# CLK_SW.net
KiCad netlist of a schematic drawn in Altium Designer
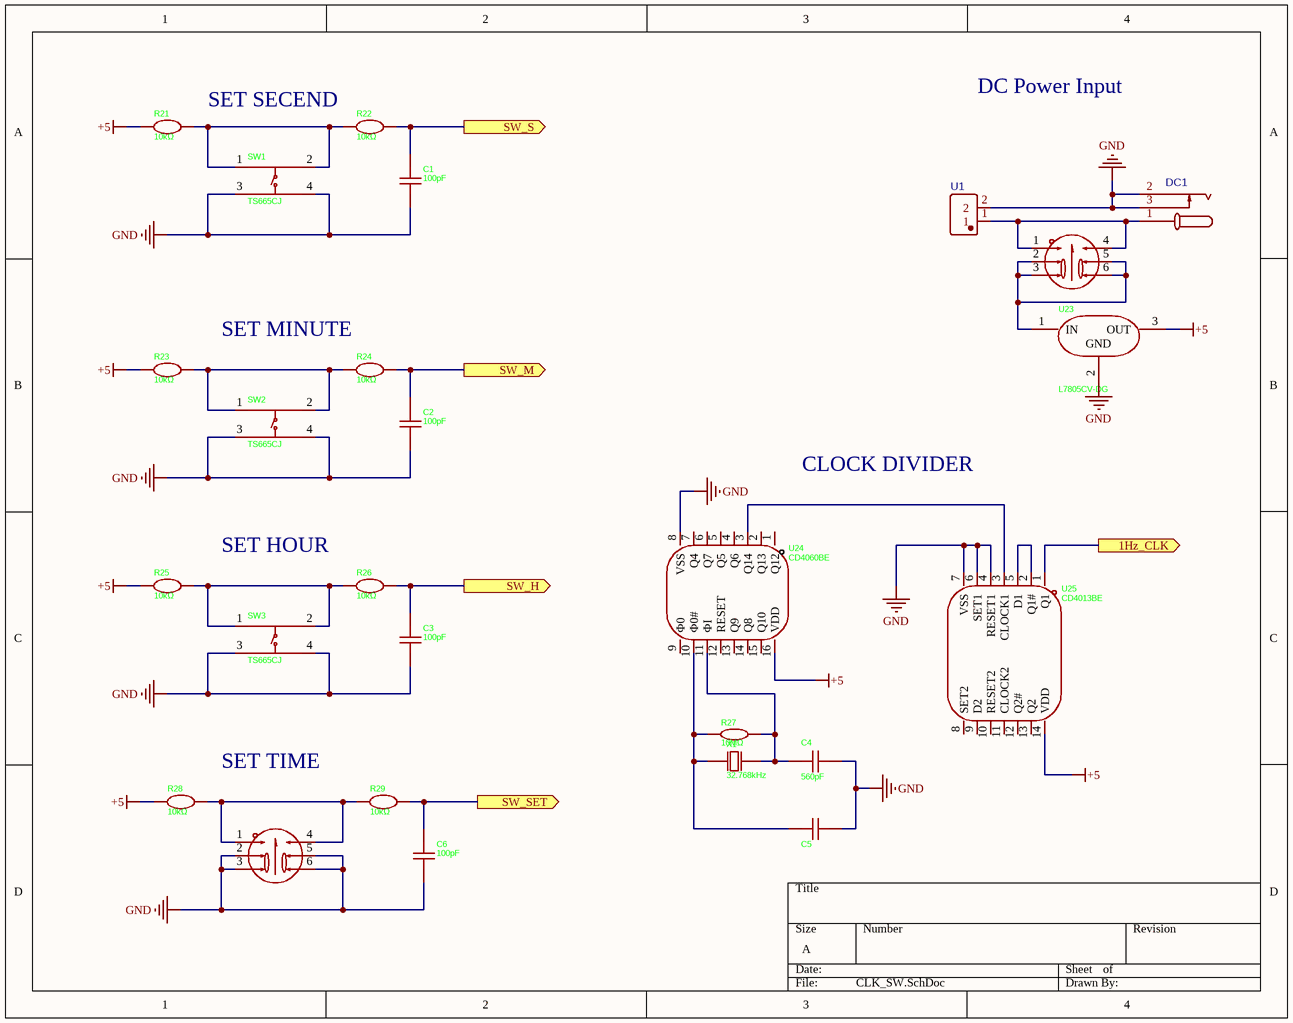
[diagram p0: CLK_SW.SchDoc]

(export (version "E")
  (design (tool "Eeschema 10.0.6"))
  (components
    (comp (ref "C1")
      (value "100pF")
      (footprint "CAP-TH_L5.0-W3.0-P5.00-D0.6-S2.45")
      (fields
        (field (name "MANUFACTURER") "SHM(南方宏明)")
        (field (name "MANUFACTURER PART") "DCT101K20Y5PF6FJ5A0")
        (field (name "TOLERANCE") "±10%")
      )
      (libsource (lib "BCD_Clock_SCH_lib") (part "Cap_100pF_50V_ceramic"))
    )
    (comp (ref "C2")
      (value "100pF")
      (footprint "CAP-TH_L5.0-W3.0-P5.00-D0.6-S2.45")
      (fields
        (field (name "MANUFACTURER") "SHM(南方宏明)")
        (field (name "MANUFACTURER PART") "DCT101K20Y5PF6FJ5A0")
        (field (name "TOLERANCE") "±10%")
      )
      (libsource (lib "BCD_Clock_SCH_lib") (part "Cap_100pF_50V_ceramic"))
    )
    (comp (ref "C3")
      (value "100pF")
      (footprint "CAP-TH_L5.0-W3.0-P5.00-D0.6-S2.45")
      (fields
        (field (name "MANUFACTURER") "SHM(南方宏明)")
        (field (name "MANUFACTURER PART") "DCT101K20Y5PF6FJ5A0")
        (field (name "TOLERANCE") "±10%")
      )
      (libsource (lib "BCD_Clock_SCH_lib") (part "Cap_100pF_50V_ceramic"))
    )
    (comp (ref "C4")
      (value "560pF")
      (footprint "CAP-TH_L8.5-W3.0-P5.00-D0.6-S2.5")
      (fields
        (field (name "MANUFACTURER") "SHM(南方宏明)")
        (field (name "MANUFACTURER PART") "DCC561J34SL F6FJ5A0")
        (field (name "TOLERANCE") "±5%")
      )
      (libsource (lib "BCD_Clock_SCH_lib") (part "Cap_560pF_50V_ceraic"))
    )
    (comp (ref "C5")
      (value "22pF")
      (footprint "CAP-TH_L7.4-W4.0-P6.40-D0.5-S1.00")
      (fields
        (field (name "MANUFACTURER") "Dersonic(德尔创)")
        (field (name "MANUFACTURER PART") "CC1H220KA1EDCH4B1100")
        (field (name "TOLERANCE") "±10%")
      )
      (libsource (lib "BCD_Clock_SCH_lib") (part "Cap_22pF_50V_ceramic"))
    )
    (comp (ref "C6")
      (value "100pF")
      (footprint "CAP-TH_L5.0-W3.0-P5.00-D0.6-S2.45")
      (fields
        (field (name "MANUFACTURER") "SHM(南方宏明)")
        (field (name "MANUFACTURER PART") "DCT101K20Y5PF6FJ5A0")
        (field (name "TOLERANCE") "±10%")
      )
      (libsource (lib "BCD_Clock_SCH_lib") (part "Cap_100pF_50V_ceramic"))
    )
    (comp (ref "DC1")
      (value "DC-005-2.5A-2.0")
      (footprint "CONN-TH_DC-005-2.5A-2.0")
      (fields (field (name "MANUFACTURER") "XKB Connection(中国星坤)") (field (name "CONTRIBUTOR") "LCSC"))
      (libsource (lib "BCD_Clock_SCH_lib") (part "DC-005-2.5A-2.0"))
    )
    (comp (ref "R21")
      (value "10kΩ")
      (footprint "RES-TH_BD2.4-L6.3-P10.30-D0.6")
      (fields
        (field (name "MANUFACTURER") "Tyohm(幸亚电阻)")
        (field (name "MANUFACTURER PART") "RN1/4W10KFT/BA1")
        (field (name "TOLERANCE") "±1%")
      )
      (libsource (lib "BCD_Clock_SCH_lib") (part "Reg_10k_0.25W"))
    )
    (comp (ref "R22")
      (value "10kΩ")
      (footprint "RES-TH_BD2.4-L6.3-P10.30-D0.6")
      (fields
        (field (name "MANUFACTURER") "Tyohm(幸亚电阻)")
        (field (name "MANUFACTURER PART") "RN1/4W10KFT/BA1")
        (field (name "TOLERANCE") "±1%")
      )
      (libsource (lib "BCD_Clock_SCH_lib") (part "Reg_10k_0.25W"))
    )
    (comp (ref "R23")
      (value "10kΩ")
      (footprint "RES-TH_BD2.4-L6.3-P10.30-D0.6")
      (fields
        (field (name "MANUFACTURER") "Tyohm(幸亚电阻)")
        (field (name "MANUFACTURER PART") "RN1/4W10KFT/BA1")
        (field (name "TOLERANCE") "±1%")
      )
      (libsource (lib "BCD_Clock_SCH_lib") (part "Reg_10k_0.25W"))
    )
    (comp (ref "R24")
      (value "10kΩ")
      (footprint "RES-TH_BD2.4-L6.3-P10.30-D0.6")
      (fields
        (field (name "MANUFACTURER") "Tyohm(幸亚电阻)")
        (field (name "MANUFACTURER PART") "RN1/4W10KFT/BA1")
        (field (name "TOLERANCE") "±1%")
      )
      (libsource (lib "BCD_Clock_SCH_lib") (part "Reg_10k_0.25W"))
    )
    (comp (ref "R25")
      (value "10kΩ")
      (footprint "RES-TH_BD2.4-L6.3-P10.30-D0.6")
      (fields
        (field (name "MANUFACTURER") "Tyohm(幸亚电阻)")
        (field (name "MANUFACTURER PART") "RN1/4W10KFT/BA1")
        (field (name "TOLERANCE") "±1%")
      )
      (libsource (lib "BCD_Clock_SCH_lib") (part "Reg_10k_0.25W"))
    )
    (comp (ref "R26")
      (value "10kΩ")
      (footprint "RES-TH_BD2.4-L6.3-P10.30-D0.6")
      (fields
        (field (name "MANUFACTURER") "Tyohm(幸亚电阻)")
        (field (name "MANUFACTURER PART") "RN1/4W10KFT/BA1")
        (field (name "TOLERANCE") "±1%")
      )
      (libsource (lib "BCD_Clock_SCH_lib") (part "Reg_10k_0.25W"))
    )
    (comp (ref "R27")
      (value "10MΩ")
      (footprint "RES-TH_BD2.2-L6.5-P10.50-D0.6")
      (fields
        (field (name "MANUFACTURER") "CCO(千志电子)")
        (field (name "MANUFACTURER PART") "CF1/4W-10MΩ±5% T")
        (field (name "TOLERANCE") "±5%")
      )
      (libsource (lib "BCD_Clock_SCH_lib") (part "Reg_10M_0.25W"))
    )
    (comp (ref "R28")
      (value "10kΩ")
      (footprint "RES-TH_BD2.4-L6.3-P10.30-D0.6")
      (fields
        (field (name "MANUFACTURER") "Tyohm(幸亚电阻)")
        (field (name "MANUFACTURER PART") "RN1/4W10KFT/BA1")
        (field (name "TOLERANCE") "±1%")
      )
      (libsource (lib "BCD_Clock_SCH_lib") (part "Reg_10k_0.25W"))
    )
    (comp (ref "R29")
      (value "10kΩ")
      (footprint "RES-TH_BD2.4-L6.3-P10.30-D0.6")
      (fields
        (field (name "MANUFACTURER") "Tyohm(幸亚电阻)")
        (field (name "MANUFACTURER PART") "RN1/4W10KFT/BA1")
        (field (name "TOLERANCE") "±1%")
      )
      (libsource (lib "BCD_Clock_SCH_lib") (part "Reg_10k_0.25W"))
    )
    (comp (ref "SW1")
      (value "TS665CJ")
      (footprint "SW-TH_4P-L6.0-W6.0-P4.50-LS6.5")
      (fields (field (name "MANUFACTURER") "SHOU HAN(首韩)"))
      (libsource (lib "BCD_Clock_SCH_lib") (part "TS665CJ"))
    )
    (comp (ref "SW2")
      (value "TS665CJ")
      (footprint "SW-TH_4P-L6.0-W6.0-P4.50-LS6.5")
      (fields (field (name "MANUFACTURER") "SHOU HAN(首韩)"))
      (libsource (lib "BCD_Clock_SCH_lib") (part "TS665CJ"))
    )
    (comp (ref "SW3")
      (value "TS665CJ")
      (footprint "SW-TH_4P-L6.0-W6.0-P4.50-LS6.5")
      (fields (field (name "MANUFACTURER") "SHOU HAN(首韩)"))
      (libsource (lib "BCD_Clock_SCH_lib") (part "TS665CJ"))
    )
    (comp (ref "U1")
      (value "DBT50G-7.62-2P")
      (footprint "CONN-TH_2P-P7.62_L15.2-W16.7-EX4.2")
      (fields
        (field (name "MANUFACTURER") "DORABO(地博电气)")
        (field (name "MANUFACTURER PART") "DBT50G-7.62-2P-BK-P")
        (field (name "CONTRIBUTOR") "LCSC")
      )
      (libsource (lib "BCD_Clock_SCH_lib") (part "DBT50G-7.62-2P"))
    )
    (comp (ref "U22")
      (value "PS-7054DVB-6PL")
      (footprint "SW-TH_6P-L7.0-W7.0-P2.00")
      (fields (field (name "MANUFACTURER") "G-Switch(品赞)"))
      (libsource (lib "BCD_Clock_SCH_lib") (part "PS-7054DVB-6PL"))
    )
    (comp (ref "U23")
      (value "L7805CV-DG")
      (footprint "TO-220-3_L10.0-W4.5-P2.54-L")
      (fields (field (name "MANUFACTURER") "ST(意法半导体)"))
      (libsource (lib "BCD_Clock_SCH_lib") (part "L7805CV-DG"))
    )
    (comp (ref "U24")
      (value "CD4060BE")
      (footprint "DIP-16_L19.8-W6.5-P2.54-LS7.6-BL")
      (fields (field (name "MANUFACTURER") "HGSEMI(华冠)"))
      (libsource (lib "BCD_Clock_SCH_lib") (part "CD4060BE"))
    )
    (comp (ref "U25")
      (value "CD4013BE")
      (footprint "DIP-14_L19.2-W6.6-P2.54-LS10.9-BL")
      (fields (field (name "MANUFACTURER") "TI(德州仪器)"))
      (libsource (lib "BCD_Clock_SCH_lib") (part "CD4013BE"))
    )
    (comp (ref "U26")
      (value "PS-7054DVB-6PL")
      (footprint "SW-TH_6P-L7.0-W7.0-P2.00")
      (fields (field (name "MANUFACTURER") "G-Switch(品赞)"))
      (libsource (lib "BCD_Clock_SCH_lib") (part "PS-7054DVB-6PL"))
    )
    (comp (ref "X1")
      (value "32.768kHz")
      (footprint "OSC-TH_BD3.1-P0.8-D0.3")
      (fields (field (name "MANUFACTURER") "ABRACON") (field (name "MANUFACTURER PART") "AB38T-32.768KHZ"))
      (libsource (lib "BCD_Clock_SCH_lib") (part "AB38T-32.768KHZ"))
    )
  )
  (nets
    (net (code "1") (name "+5") (class "Default")
      (node (ref "R21") (pin "2") (pinfunction "2_2") (pintype "passive"))
      (node (ref "R23") (pin "2") (pinfunction "2_2") (pintype "passive"))
      (node (ref "R25") (pin "2") (pinfunction "2_2") (pintype "passive"))
      (node (ref "R28") (pin "2") (pinfunction "2_2") (pintype "passive"))
      (node (ref "U23") (pin "3") (pinfunction "OUT_3") (pintype "passive"))
      (node (ref "U24") (pin "16") (pinfunction "VDD_16") (pintype "passive"))
      (node (ref "U25") (pin "14") (pinfunction "VDD_14") (pintype "passive"))
    )
    (net (code "2") (name "/1Hz_CLK") (class "Default")
      (node (ref "U25") (pin "1") (pinfunction "Q1_1") (pintype "passive"))
    )
    (net (code "3") (name "/SW_H") (class "Default")
      (node (ref "C3") (pin "2") (pinfunction "2_2") (pintype "passive"))
      (node (ref "R26") (pin "1") (pinfunction "1_1") (pintype "passive"))
    )
    (net (code "4") (name "/SW_M") (class "Default")
      (node (ref "C2") (pin "2") (pinfunction "2_2") (pintype "passive"))
      (node (ref "R24") (pin "1") (pinfunction "1_1") (pintype "passive"))
    )
    (net (code "5") (name "/SW_S") (class "Default")
      (node (ref "C1") (pin "2") (pinfunction "2_2") (pintype "passive"))
      (node (ref "R22") (pin "1") (pinfunction "1_1") (pintype "passive"))
    )
    (net (code "6") (name "/SW_SET") (class "Default")
      (node (ref "C6") (pin "2") (pinfunction "2_2") (pintype "passive"))
      (node (ref "R29") (pin "1") (pinfunction "1_1") (pintype "passive"))
    )
    (net (code "7") (name "GND") (class "Default")
      (node (ref "C1") (pin "1") (pinfunction "1_1") (pintype "passive"))
      (node (ref "C2") (pin "1") (pinfunction "1_1") (pintype "passive"))
      (node (ref "C3") (pin "1") (pinfunction "1_1") (pintype "passive"))
      (node (ref "C4") (pin "1") (pinfunction "1_1") (pintype "passive"))
      (node (ref "C5") (pin "1") (pinfunction "1_1") (pintype "passive"))
      (node (ref "C6") (pin "1") (pinfunction "1_1") (pintype "passive"))
      (node (ref "DC1") (pin "2") (pinfunction "2_2") (pintype "passive"))
      (node (ref "DC1") (pin "3") (pinfunction "3_3") (pintype "passive"))
      (node (ref "SW1") (pin "3") (pinfunction "C_3") (pintype "passive"))
      (node (ref "SW1") (pin "4") (pinfunction "D_4") (pintype "passive"))
      (node (ref "SW2") (pin "3") (pinfunction "C_3") (pintype "passive"))
      (node (ref "SW2") (pin "4") (pinfunction "D_4") (pintype "passive"))
      (node (ref "SW3") (pin "3") (pinfunction "C_3") (pintype "passive"))
      (node (ref "SW3") (pin "4") (pinfunction "D_4") (pintype "passive"))
      (node (ref "U1") (pin "2") (pinfunction "2_2") (pintype "passive"))
      (node (ref "U23") (pin "2") (pinfunction "GND_2") (pintype "passive"))
      (node (ref "U24") (pin "8") (pinfunction "VSS_8") (pintype "passive"))
      (node (ref "U25") (pin "4") (pinfunction "RESET1_4") (pintype "passive"))
      (node (ref "U25") (pin "6") (pinfunction "SET1_6") (pintype "passive"))
      (node (ref "U25") (pin "7") (pinfunction "VSS_7") (pintype "passive"))
      (node (ref "U26") (pin "2") (pinfunction "2_2") (pintype "passive"))
      (node (ref "U26") (pin "3") (pinfunction "3_3") (pintype "passive"))
      (node (ref "U26") (pin "5") (pinfunction "5_5") (pintype "passive"))
      (node (ref "U26") (pin "6") (pinfunction "6_6") (pintype "passive"))
    )
    (net (code "8") (name "Net-(DC1-Pad1)") (class "Default")
      (node (ref "DC1") (pin "1") (pinfunction "1_1") (pintype "passive"))
      (node (ref "U1") (pin "1") (pinfunction "1_1") (pintype "passive"))
      (node (ref "U22") (pin "1") (pinfunction "1_1") (pintype "passive"))
      (node (ref "U22") (pin "4") (pinfunction "4_4") (pintype "passive"))
    )
    (net (code "9") (name "Net-(R28-Pad1)") (class "Default")
      (node (ref "R28") (pin "1") (pinfunction "1_1") (pintype "passive"))
      (node (ref "R29") (pin "2") (pinfunction "2_2") (pintype "passive"))
      (node (ref "U26") (pin "1") (pinfunction "1_1") (pintype "passive"))
      (node (ref "U26") (pin "4") (pinfunction "4_4") (pintype "passive"))
    )
    (net (code "10") (name "Net-(SW1-A)") (class "Default")
      (node (ref "R21") (pin "1") (pinfunction "1_1") (pintype "passive"))
      (node (ref "R22") (pin "2") (pinfunction "2_2") (pintype "passive"))
      (node (ref "SW1") (pin "1") (pinfunction "A_1") (pintype "passive"))
      (node (ref "SW1") (pin "2") (pinfunction "B_2") (pintype "passive"))
    )
    (net (code "11") (name "Net-(SW2-A)") (class "Default")
      (node (ref "R23") (pin "1") (pinfunction "1_1") (pintype "passive"))
      (node (ref "R24") (pin "2") (pinfunction "2_2") (pintype "passive"))
      (node (ref "SW2") (pin "1") (pinfunction "A_1") (pintype "passive"))
      (node (ref "SW2") (pin "2") (pinfunction "B_2") (pintype "passive"))
    )
    (net (code "12") (name "Net-(SW3-A)") (class "Default")
      (node (ref "R25") (pin "1") (pinfunction "1_1") (pintype "passive"))
      (node (ref "R26") (pin "2") (pinfunction "2_2") (pintype "passive"))
      (node (ref "SW3") (pin "1") (pinfunction "A_1") (pintype "passive"))
      (node (ref "SW3") (pin "2") (pinfunction "B_2") (pintype "passive"))
    )
    (net (code "13") (name "Net-(U23-IN)") (class "Default")
      (node (ref "U22") (pin "2") (pinfunction "2_2") (pintype "passive"))
      (node (ref "U22") (pin "3") (pinfunction "3_3") (pintype "passive"))
      (node (ref "U22") (pin "5") (pinfunction "5_5") (pintype "passive"))
      (node (ref "U22") (pin "6") (pinfunction "6_6") (pintype "passive"))
      (node (ref "U23") (pin "1") (pinfunction "IN_1") (pintype "passive"))
    )
    (net (code "14") (name "Net-(U24-Q14)") (class "Default")
      (node (ref "U24") (pin "3") (pinfunction "Q14_3") (pintype "passive"))
      (node (ref "U25") (pin "3") (pinfunction "CLOCK1_3") (pintype "passive"))
    )
    (net (code "15") (name "Net-(U24-Φ0#)") (class "Default")
      (node (ref "C5") (pin "2") (pinfunction "2_2") (pintype "passive"))
      (node (ref "R27") (pin "2") (pinfunction "2_2") (pintype "passive"))
      (node (ref "U24") (pin "10") (pinfunction "Φ0#_10") (pintype "passive"))
      (node (ref "X1") (pin "1") (pinfunction "OSC1_1") (pintype "passive"))
    )
    (net (code "16") (name "Net-(U24-ΦI)") (class "Default")
      (node (ref "C4") (pin "2") (pinfunction "2_2") (pintype "passive"))
      (node (ref "R27") (pin "1") (pinfunction "1_1") (pintype "passive"))
      (node (ref "U24") (pin "11") (pinfunction "ΦI_11") (pintype "passive"))
      (node (ref "X1") (pin "2") (pinfunction "OSC2_2") (pintype "passive"))
    )
    (net (code "17") (name "Net-(U25-D1)") (class "Default")
      (node (ref "U25") (pin "2") (pinfunction "Q1#_2") (pintype "passive"))
      (node (ref "U25") (pin "5") (pinfunction "D1_5") (pintype "passive"))
    )
    (net (code "18") (name "unconnected-(U24-Q4-Pad7)") (class "Default")
      (node (ref "U24") (pin "7") (pinfunction "Q4_7") (pintype "passive"))
    )
    (net (code "19") (name "unconnected-(U24-Q5-Pad5)") (class "Default")
      (node (ref "U24") (pin "5") (pinfunction "Q5_5") (pintype "passive"))
    )
    (net (code "20") (name "unconnected-(U24-Q6-Pad4)") (class "Default")
      (node (ref "U24") (pin "4") (pinfunction "Q6_4") (pintype "passive"))
    )
    (net (code "21") (name "unconnected-(U24-Q7-Pad6)") (class "Default")
      (node (ref "U24") (pin "6") (pinfunction "Q7_6") (pintype "passive"))
    )
    (net (code "22") (name "unconnected-(U24-Q8-Pad14)") (class "Default")
      (node (ref "U24") (pin "14") (pinfunction "Q8_14") (pintype "passive"))
    )
    (net (code "23") (name "unconnected-(U24-Q9-Pad13)") (class "Default")
      (node (ref "U24") (pin "13") (pinfunction "Q9_13") (pintype "passive"))
    )
    (net (code "24") (name "unconnected-(U24-Q10-Pad15)") (class "Default")
      (node (ref "U24") (pin "15") (pinfunction "Q10_15") (pintype "passive"))
    )
    (net (code "25") (name "unconnected-(U24-Q12-Pad1)") (class "Default")
      (node (ref "U24") (pin "1") (pinfunction "Q12_1") (pintype "passive"))
    )
    (net (code "26") (name "unconnected-(U24-Q13-Pad2)") (class "Default")
      (node (ref "U24") (pin "2") (pinfunction "Q13_2") (pintype "passive"))
    )
    (net (code "27") (name "unconnected-(U24-RESET-Pad12)") (class "Default")
      (node (ref "U24") (pin "12") (pinfunction "RESET_12") (pintype "passive"))
    )
    (net (code "28") (name "unconnected-(U24-Φ0-Pad9)") (class "Default")
      (node (ref "U24") (pin "9") (pinfunction "Φ0_9") (pintype "passive"))
    )
    (net (code "29") (name "unconnected-(U25-CLOCK2-Pad11)") (class "Default")
      (node (ref "U25") (pin "11") (pinfunction "CLOCK2_11") (pintype "passive"))
    )
    (net (code "30") (name "unconnected-(U25-D2-Pad9)") (class "Default")
      (node (ref "U25") (pin "9") (pinfunction "D2_9") (pintype "passive"))
    )
    (net (code "31") (name "unconnected-(U25-Q2#-Pad12)") (class "Default")
      (node (ref "U25") (pin "12") (pinfunction "Q2#_12") (pintype "passive"))
    )
    (net (code "32") (name "unconnected-(U25-Q2-Pad13)") (class "Default")
      (node (ref "U25") (pin "13") (pinfunction "Q2_13") (pintype "passive"))
    )
    (net (code "33") (name "unconnected-(U25-RESET2-Pad10)") (class "Default")
      (node (ref "U25") (pin "10") (pinfunction "RESET2_10") (pintype "passive"))
    )
    (net (code "34") (name "unconnected-(U25-SET2-Pad8)") (class "Default")
      (node (ref "U25") (pin "8") (pinfunction "SET2_8") (pintype "passive"))
    )
  )
)
